# MEchaduino_03.net
KiCad netlist of a schematic drawn in EAGLE
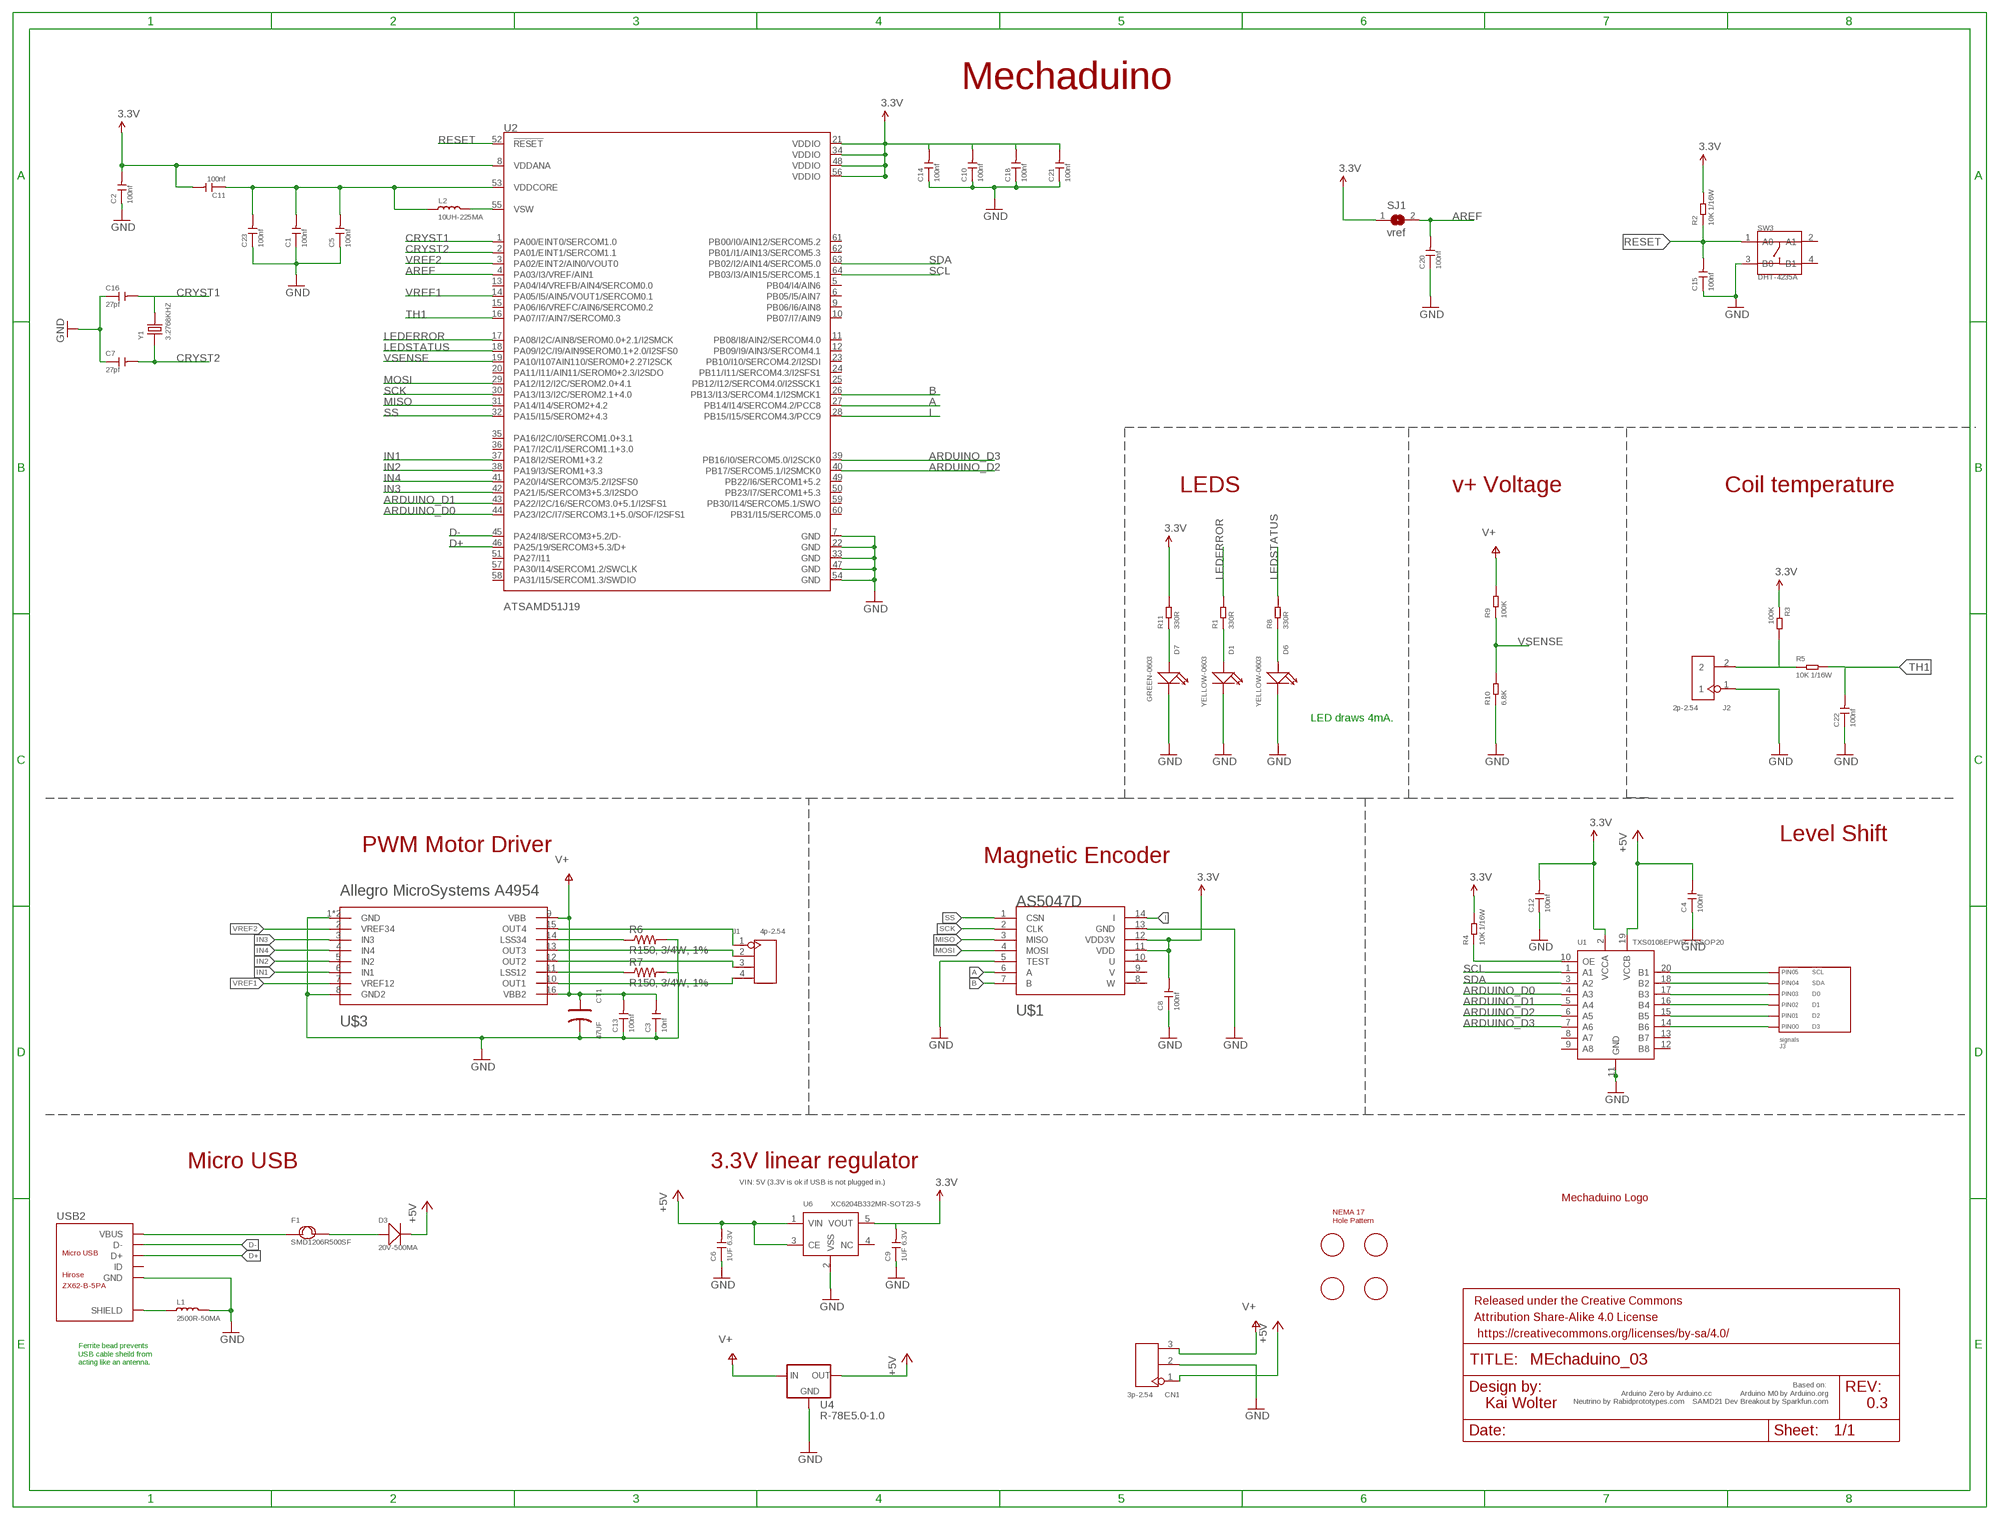
[diagram p0: schematic, sheet 1]

(export (version "E")
  (design (tool "Eeschema 10.0.6"))
  (components
    (comp (ref "C1")
      (value "100nf")
      (footprint "eagle-import:C0402")
      (fields (field (name "MPN") "CC0402KRX7R8BB104"))
      (libsource (lib "eagle-import") (part "CERAMIC-100NF-25V-10%-X7R(0402)"))
    )
    (comp (ref "C2")
      (value "100nf")
      (footprint "eagle-import:C0402")
      (fields (field (name "MPN") "CC0402KRX7R8BB104"))
      (libsource (lib "eagle-import") (part "CERAMIC-100NF-25V-10%-X7R(0402)"))
    )
    (comp (ref "C3")
      (value "10nf")
      (footprint "eagle-import:C0603")
      (fields (field (name "MPN") "CC0603KRX7R9BB103"))
      (libsource (lib "eagle-import") (part "CERAMIC-10NF-50V-10%-X7R(0603)"))
    )
    (comp (ref "C4")
      (value "100nf")
      (footprint "eagle-import:C0402")
      (fields (field (name "MPN") "CC0402KRX7R8BB104"))
      (libsource (lib "eagle-import") (part "CERAMIC-100NF-25V-10%-X7R(0402)"))
    )
    (comp (ref "C5")
      (value "100nf")
      (footprint "eagle-import:C0402")
      (fields (field (name "MPN") "CC0402KRX7R8BB104"))
      (libsource (lib "eagle-import") (part "CERAMIC-100NF-25V-10%-X7R(0402)"))
    )
    (comp (ref "C6")
      (value "1UF 6.3V")
      (footprint "eagle-import:C0402")
      (fields (field (name "MPN") "CC0402KRX5R5BB105"))
      (libsource (lib "eagle-import") (part "CERAMIC-1UF-6.3V-10%-X5R(0402)"))
    )
    (comp (ref "C7")
      (value "27pf")
      (footprint "eagle-import:C0402")
      (fields (field (name "MPN") "CC0402JRNPO9BN270"))
      (libsource (lib "eagle-import") (part "CERAMIC-27PF-50V-5%-NPO(0402)"))
    )
    (comp (ref "C8")
      (value "100nf")
      (footprint "eagle-import:C0402")
      (fields (field (name "MPN") "CC0402KRX7R8BB104"))
      (libsource (lib "eagle-import") (part "CERAMIC-100NF-25V-10%-X7R(0402)"))
    )
    (comp (ref "C9")
      (value "1UF 6.3V")
      (footprint "eagle-import:C0402")
      (fields (field (name "MPN") "CC0402KRX5R5BB105"))
      (libsource (lib "eagle-import") (part "CERAMIC-1UF-6.3V-10%-X5R(0402)"))
    )
    (comp (ref "C10")
      (value "100nf")
      (footprint "eagle-import:C0402")
      (fields (field (name "MPN") "CC0402KRX7R8BB104"))
      (libsource (lib "eagle-import") (part "CERAMIC-100NF-25V-10%-X7R(0402)"))
    )
    (comp (ref "C11")
      (value "100nf")
      (footprint "eagle-import:C0402")
      (fields (field (name "MPN") "CC0402KRX7R8BB104"))
      (libsource (lib "eagle-import") (part "CERAMIC-100NF-25V-10%-X7R(0402)"))
    )
    (comp (ref "C12")
      (value "100nf")
      (footprint "eagle-import:C0402")
      (fields (field (name "MPN") "CC0402KRX7R8BB104"))
      (libsource (lib "eagle-import") (part "CERAMIC-100NF-25V-10%-X7R(0402)"))
    )
    (comp (ref "C13")
      (value "100nf")
      (footprint "eagle-import:C0603")
      (fields (field (name "MPN") "CC0603KRX7R9BB104"))
      (libsource (lib "eagle-import") (part "CERAMIC-100NF-50V-10%-X7R(0603)"))
    )
    (comp (ref "C14")
      (value "100nf")
      (footprint "eagle-import:C0402")
      (fields (field (name "MPN") "CC0402KRX7R8BB104"))
      (libsource (lib "eagle-import") (part "CERAMIC-100NF-25V-10%-X7R(0402)"))
    )
    (comp (ref "C15")
      (value "100nf")
      (footprint "eagle-import:C0402")
      (fields (field (name "MPN") "CC0402KRX7R8BB104"))
      (libsource (lib "eagle-import") (part "CERAMIC-100NF-25V-10%-X7R(0402)"))
    )
    (comp (ref "C16")
      (value "27pf")
      (footprint "eagle-import:C0402")
      (fields (field (name "MPN") "CC0402JRNPO9BN270"))
      (libsource (lib "eagle-import") (part "CERAMIC-27PF-50V-5%-NPO(0402)"))
    )
    (comp (ref "C18")
      (value "100nf")
      (footprint "eagle-import:C0402")
      (fields (field (name "MPN") "CC0402KRX7R8BB104"))
      (libsource (lib "eagle-import") (part "CERAMIC-100NF-25V-10%-X7R(0402)"))
    )
    (comp (ref "C20")
      (value "100nf")
      (footprint "eagle-import:C0402")
      (fields (field (name "MPN") "CC0402KRX7R8BB104"))
      (libsource (lib "eagle-import") (part "CERAMIC-100NF-25V-10%-X7R(0402)"))
    )
    (comp (ref "C21")
      (value "100nf")
      (footprint "eagle-import:C0402")
      (fields (field (name "MPN") "CC0402KRX7R8BB104"))
      (libsource (lib "eagle-import") (part "CERAMIC-100NF-25V-10%-X7R(0402)"))
    )
    (comp (ref "C22")
      (value "100nf")
      (footprint "eagle-import:C0402")
      (fields (field (name "MPN") "CC0402KRX7R8BB104"))
      (libsource (lib "eagle-import") (part "CERAMIC-100NF-25V-10%-X7R(0402)"))
    )
    (comp (ref "C23")
      (value "100nf")
      (footprint "eagle-import:C0402")
      (fields (field (name "MPN") "CC0402KRX7R8BB104"))
      (libsource (lib "eagle-import") (part "CERAMIC-100NF-25V-10%-X7R(0402)"))
    )
    (comp (ref "CN1")
      (value "3p-2.54")
      (footprint "eagle-import:H3-2.54")
      (libsource (lib "eagle-import") (part "DIP-BLACK-MALE-HEADER-VERT(3P-2.54)"))
    )
    (comp (ref "CT1")
      (value "47UF")
      (footprint "eagle-import:ELECTRO-SMD-C-6MM")
      (fields (field (name "MPN") "CS1E470M-CRE54"))
      (libsource (lib "eagle-import") (part "ALUMINUM-SMD-47UF-25V(D6.3-H5.3MM)"))
    )
    (comp (ref "D1")
      (value "YELLOW-0603")
      (footprint "eagle-import:LED-0603")
      (fields (field (name "MPN") "19-217-Y5C-AM1N1VY-3T"))
      (libsource (lib "eagle-import") (part "SMD-LED-CLEAR-YELLOW(0603)"))
    )
    (comp (ref "D3")
      (value "20V-500MA")
      (footprint "eagle-import:SOD-123")
      (fields (field (name "MPN") "SS0520-7-F"))
      (libsource (lib "eagle-import") (part "SMD-DIODE-SCHOTTKY-20V-500MA(SOD-123)"))
    )
    (comp (ref "D6")
      (value "YELLOW-0603")
      (footprint "eagle-import:LED-0603")
      (fields (field (name "MPN") "19-217-Y5C-AM1N1VY-3T"))
      (libsource (lib "eagle-import") (part "SMD-LED-CLEAR-YELLOW(0603)"))
    )
    (comp (ref "D7")
      (value "GREEN-0603")
      (footprint "eagle-import:LED-0603")
      (fields (field (name "MPN") "19-217-G7C-AN1P2-3T"))
      (libsource (lib "eagle-import") (part "SMD-LED-CLEAR-GREEN(0603)"))
    )
    (comp (ref "F1")
      (value "SMD1206R500SF")
      (footprint "eagle-import:F1206")
      (libsource (lib "eagle-import") (part "SMD-PPTC-500MA(1206)"))
    )
    (comp (ref "FRAME1")
      (value "FRAME-LEDGER")
      (footprint "eagle-import:CREATIVE_COMMONS")
      (libsource (lib "eagle-import") (part "FRAME-LEDGER"))
    )
    (comp (ref "J1")
      (value "4p-2.54")
      (footprint "eagle-import:H4-2.54")
      (fields (field (name "MPN") "P125-1104A0BS116A1"))
      (libsource (lib "eagle-import") (part "DIP-BLACK-MALE-HEADER-VERT(4P-2.54)"))
    )
    (comp (ref "J2")
      (value "2p-2.54")
      (footprint "eagle-import:H2-2.54")
      (fields (field (name "MPN") "P125-1102A0BS116A1"))
      (libsource (lib "eagle-import") (part "DIP-BLACK-MALE-HEADER-VERT(2P-2.54)"))
    )
    (comp (ref "J3")
      (value "signals")
      (footprint "eagle-import:PTH_2.54MM_01X06")
      (fields
        (field (name "LABEL00") "D3")
        (field (name "LABEL01") "D2")
        (field (name "LABEL02") "D1")
        (field (name "LABEL03") "D0")
        (field (name "LABEL04") "SDA")
        (field (name "LABEL05") "SCL")
      )
      (libsource (lib "eagle-import") (part "HEADER_01X06_PTH_2.54MM"))
    )
    (comp (ref "L1")
      (value "2500R-50MA")
      (footprint "eagle-import:L0603")
      (libsource (lib "eagle-import") (part "SMD-FERRITE-BEAD-2500R-50MA(0603)"))
    )
    (comp (ref "L2")
      (value "10UH-225MA")
      (footprint "eagle-import:L0806")
      (fields (field (name "MPN") "LQH2MCN100K02L"))
      (libsource (lib "eagle-import") (part "SMD-INDUCTOR-10UH-225MA-10%(0806)"))
    )
    (comp (ref "R1")
      (value "330R")
      (footprint "eagle-import:R0402")
      (fields (field (name "MPN") "RC0402FR-07330RL"))
      (libsource (lib "eagle-import") (part "SMD-RES-330R-1%-1/16W(0402)"))
    )
    (comp (ref "R2")
      (value "10K 1/16W")
      (footprint "eagle-import:R0402")
      (fields (field (name "MPN") "RC0402FR-0710KL"))
      (libsource (lib "eagle-import") (part "SMD-RES-10K-1%-1/16W(0402)"))
    )
    (comp (ref "R3")
      (value "100K")
      (footprint "eagle-import:R0402")
      (fields (field (name "MPN") "RC0402FR-07100KL"))
      (libsource (lib "eagle-import") (part "SMD-RES-100K-1%-1/16W(0402)"))
    )
    (comp (ref "R4")
      (value "10K 1/16W")
      (footprint "eagle-import:R0402")
      (fields (field (name "MPN") "RC0402FR-0710KL"))
      (libsource (lib "eagle-import") (part "SMD-RES-10K-1%-1/16W(0402)"))
    )
    (comp (ref "R5")
      (value "10K 1/16W")
      (footprint "eagle-import:R0402")
      (fields (field (name "MPN") "RC0402FR-0710KL"))
      (libsource (lib "eagle-import") (part "SMD-RES-10K-1%-1/16W(0402)"))
    )
    (comp (ref "R6")
      (value "R150, 3/4W, 1%")
      (footprint "eagle-import:R1206")
      (fields (field (name "MPN") "KRL1632E-M-R150-F-T5 "))
      (libsource (lib "eagle-import") (part "R-US_R1206"))
    )
    (comp (ref "R7")
      (value "R150, 3/4W, 1%")
      (footprint "eagle-import:R1206")
      (fields (field (name "MPN") "KRL1632E-M-R150-F-T5 "))
      (libsource (lib "eagle-import") (part "R-US_R1206"))
    )
    (comp (ref "R8")
      (value "330R")
      (footprint "eagle-import:R0402")
      (fields (field (name "MPN") "RC0402FR-07330RL"))
      (libsource (lib "eagle-import") (part "SMD-RES-330R-1%-1/16W(0402)"))
    )
    (comp (ref "R9")
      (value "100K")
      (footprint "eagle-import:R0402")
      (fields (field (name "MPN") "RC0402FR-07100KL"))
      (libsource (lib "eagle-import") (part "SMD-RES-100K-1%-1/16W(0402)"))
    )
    (comp (ref "R10")
      (value "6.8K")
      (footprint "eagle-import:R0603")
      (fields (field (name "MPN") "RC0805JR-07220KL"))
      (libsource (lib "eagle-import") (part "SMD-RES-6.8K-1%-1/10W(0603)"))
    )
    (comp (ref "R11")
      (value "330R")
      (footprint "eagle-import:R0402")
      (fields (field (name "MPN") "RC0402FR-07330RL"))
      (libsource (lib "eagle-import") (part "SMD-RES-330R-1%-1/16W(0402)"))
    )
    (comp (ref "SJ1")
      (value "vref")
      (footprint "eagle-import:SJ")
      (libsource (lib "eagle-import") (part "SJ"))
    )
    (comp (ref "SW3")
      (value "DHT-4235A")
      (footprint "eagle-import:SW4-SMD-4.2X3.2X2.5MM")
      (libsource (lib "eagle-import") (part "SMD-BUTTON-TOP-DHT-4235A(4P-4.2X3.2MM)"))
    )
    (comp (ref "U$1")
      (value "AS5047D")
      (footprint "eagle-import:TSSOP14")
      (fields (field (name "MPN") "AS5047D-ATSM "))
      (libsource (lib "eagle-import") (part "AS5047D"))
    )
    (comp (ref "U$2")
      (value "NEMA17_HOLE_PATTERNNEW")
      (footprint "eagle-import:NEMA17_HOLE_PATTERN_2")
      (libsource (lib "eagle-import") (part "NEMA17_HOLE_PATTERNNEW"))
    )
    (comp (ref "U$3")
      (value "Allegro MicroSystems A4954")
      (footprint "eagle-import:TSSOP16_THERM")
      (fields (field (name "MPN") "A4953ELJTR-T "))
      (libsource (lib "eagle-import") (part "AVAGO_DRIVERTHERM"))
    )
    (comp (ref "U$4")
      (value "MECHADUINO_LOGO")
      (footprint "eagle-import:MECHADUINO_LOGO")
      (libsource (lib "eagle-import") (part "MECHADUINO_LOGO"))
    )
    (comp (ref "U1")
      (value "TXS0108EPWR-TSSOP20")
      (footprint "eagle-import:TSSOP20-0.65-6.5X4.4MM")
      (fields (field (name "MPN") "TXS0108EPWR"))
      (libsource (lib "eagle-import") (part "LOGIC-TXS0108EPWR(TSSOP20)"))
    )
    (comp (ref "U2")
      (value "ATSAMD51J19")
      (footprint "eagle-import:TQFP64")
      (fields (field (name "MPN") "ATSAMD51J19A-AU"))
      (libsource (lib "eagle-import") (part "ATSAMD51J19"))
    )
    (comp (ref "U4")
      (value "R-78E5.0-1.0")
      (footprint "eagle-import:DC-DC_CONVERTER_78XX")
      (libsource (lib "eagle-import") (part "R-78E5.0-1.0"))
    )
    (comp (ref "U6")
      (value "XC6204B332MR-SOT23-5")
      (footprint "eagle-import:SOT-23-5")
      (fields (field (name "MPN") "XC6204B332MR"))
      (libsource (lib "eagle-import") (part "PMIC-LDO-XC6204B332MR(SOT23-5)"))
    )
    (comp (ref "USB2")
      (value "ZX62-B-5PA")
      (footprint "eagle-import:MICRO-USB5+6P-SMD-0.65-AB")
      (libsource (lib "eagle-import") (part "MICRO-USB-SMD(ZX62-B-5PA)"))
    )
    (comp (ref "Y1")
      (value "3.2768KHZ")
      (footprint "eagle-import:X2-SMD-L2.0X1.2X0.55MM")
      (fields (field (name "MPN") "FC-12M"))
      (libsource (lib "eagle-import") (part "SMD-CRYSTAL-32.768KHZ-12.5PF-20PPM-90K(2P-L2.0X1.2MM)"))
    )
  )
  (nets
    (net (code "1") (name "+5V") (class "Default")
      (node (ref "C4") (pin "2") (pinfunction "2_2") (pintype "passive"))
      (node (ref "C6") (pin "2") (pinfunction "2_2") (pintype "passive"))
      (node (ref "CN1") (pin "1") (pinfunction "P$1_1") (pintype "bidirectional"))
      (node (ref "D3") (pin "-") (pinfunction "-_-") (pintype "passive"))
      (node (ref "U1") (pin "19") (pinfunction "VCCB_19") (pintype "bidirectional"))
      (node (ref "U4") (pin "VOUT") (pinfunction "OUT_VOUT") (pintype "passive"))
      (node (ref "U6") (pin "1") (pinfunction "VIN_1") (pintype "input"))
      (node (ref "U6") (pin "3") (pinfunction "CE_3") (pintype "bidirectional"))
    )
    (net (code "2") (name "/ARDUINO_D0") (class "Default")
      (node (ref "U1") (pin "4") (pinfunction "A3_4") (pintype "bidirectional"))
      (node (ref "U2") (pin "44") (pinfunction "PA23/I2C/I7/SERCOM3.1+5.0/SOF/I2SFS1_44") (pintype "bidirectional"))
    )
    (net (code "3") (name "/ARDUINO_D1") (class "Default")
      (node (ref "U1") (pin "5") (pinfunction "A4_5") (pintype "bidirectional"))
      (node (ref "U2") (pin "43") (pinfunction "PA22/I2C/16/SERCOM3.0+5.1/I2SFS1_43") (pintype "bidirectional"))
    )
    (net (code "4") (name "/ARDUINO_D2") (class "Default")
      (node (ref "U1") (pin "6") (pinfunction "A5_6") (pintype "bidirectional"))
      (node (ref "U2") (pin "40") (pinfunction "PB17/SERCOM5.1/I2SMCK0_40") (pintype "bidirectional"))
    )
    (net (code "5") (name "/ARDUINO_D3") (class "Default")
      (node (ref "U1") (pin "7") (pinfunction "A6_7") (pintype "bidirectional"))
      (node (ref "U2") (pin "39") (pinfunction "PB16/I0/SERCOM5.0/I2SCK0_39") (pintype "bidirectional"))
    )
    (net (code "6") (name "/AREF") (class "Default")
      (node (ref "C20") (pin "2") (pinfunction "2_2") (pintype "passive"))
      (node (ref "SJ1") (pin "2") (pinfunction "2_2") (pintype "passive"))
      (node (ref "U2") (pin "4") (pinfunction "PA03/I3/VREF/AIN1_4") (pintype "bidirectional"))
    )
    (net (code "7") (name "/CRYST1") (class "Default")
      (node (ref "C16") (pin "2") (pinfunction "2_2") (pintype "passive"))
      (node (ref "U2") (pin "1") (pinfunction "PA00/EINT0/SERCOM1.0_1") (pintype "bidirectional"))
      (node (ref "Y1") (pin "2") (pinfunction "2_2") (pintype "passive"))
    )
    (net (code "8") (name "/CRYST2") (class "Default")
      (node (ref "C7") (pin "2") (pinfunction "2_2") (pintype "passive"))
      (node (ref "U2") (pin "2") (pinfunction "PA01/EINT1/SERCOM1.1_2") (pintype "bidirectional"))
      (node (ref "Y1") (pin "1") (pinfunction "1_1") (pintype "passive"))
    )
    (net (code "9") (name "/LEDERROR") (class "Default")
      (node (ref "R1") (pin "2") (pinfunction "2_2") (pintype "passive"))
      (node (ref "U2") (pin "17") (pinfunction "PA08/I2C/AIN8/SEROM0.0+2.1/I2SMCK_17") (pintype "bidirectional"))
    )
    (net (code "10") (name "/LEDSTATUS") (class "Default")
      (node (ref "R8") (pin "2") (pinfunction "2_2") (pintype "passive"))
      (node (ref "U2") (pin "18") (pinfunction "PA09/I2C/I9/AIN9SEROM0.1+2.0/I2SFS0_18") (pintype "bidirectional"))
    )
    (net (code "11") (name "/SCL") (class "Default")
      (node (ref "U1") (pin "1") (pinfunction "A1_1") (pintype "bidirectional"))
      (node (ref "U2") (pin "64") (pinfunction "PB03/I3/AIN15/SERCOM5.1_64") (pintype "bidirectional"))
    )
    (net (code "12") (name "/SDA") (class "Default")
      (node (ref "U1") (pin "3") (pinfunction "A2_3") (pintype "bidirectional"))
      (node (ref "U2") (pin "63") (pinfunction "PB02/I2/AIN14/SERCOM5.0_63") (pintype "bidirectional"))
    )
    (net (code "13") (name "/VSENSE") (class "Default")
      (node (ref "R10") (pin "2") (pinfunction "2_2") (pintype "passive"))
      (node (ref "R9") (pin "1") (pinfunction "1_1") (pintype "passive"))
      (node (ref "U2") (pin "19") (pinfunction "PA10/I107AIN110/SEROM0+2.27I2SCK_19") (pintype "bidirectional"))
    )
    (net (code "14") (name "3.3V") (class "Default")
      (node (ref "C10") (pin "2") (pinfunction "2_2") (pintype "passive"))
      (node (ref "C11") (pin "2") (pinfunction "2_2") (pintype "passive"))
      (node (ref "C12") (pin "2") (pinfunction "2_2") (pintype "passive"))
      (node (ref "C14") (pin "2") (pinfunction "2_2") (pintype "passive"))
      (node (ref "C18") (pin "2") (pinfunction "2_2") (pintype "passive"))
      (node (ref "C2") (pin "2") (pinfunction "2_2") (pintype "passive"))
      (node (ref "C21") (pin "2") (pinfunction "2_2") (pintype "passive"))
      (node (ref "C8") (pin "2") (pinfunction "2_2") (pintype "passive"))
      (node (ref "C9") (pin "2") (pinfunction "2_2") (pintype "passive"))
      (node (ref "R11") (pin "2") (pinfunction "2_2") (pintype "passive"))
      (node (ref "R2") (pin "2") (pinfunction "2_2") (pintype "passive"))
      (node (ref "R3") (pin "1") (pinfunction "1_1") (pintype "passive"))
      (node (ref "R4") (pin "2") (pinfunction "2_2") (pintype "passive"))
      (node (ref "SJ1") (pin "1") (pinfunction "1_1") (pintype "passive"))
      (node (ref "U$1") (pin "11") (pinfunction "VDD_11") (pintype "bidirectional"))
      (node (ref "U$1") (pin "12") (pinfunction "VDD3V_12") (pintype "bidirectional"))
      (node (ref "U1") (pin "2") (pinfunction "VCCA_2") (pintype "bidirectional"))
      (node (ref "U2") (pin "21") (pinfunction "VDDIO_21") (pintype "bidirectional"))
      (node (ref "U2") (pin "34") (pinfunction "VDDIO_34") (pintype "bidirectional"))
      (node (ref "U2") (pin "48") (pinfunction "VDDIO_48") (pintype "bidirectional"))
      (node (ref "U2") (pin "56") (pinfunction "VDDIO_56") (pintype "bidirectional"))
      (node (ref "U2") (pin "8") (pinfunction "VDDANA_8") (pintype "bidirectional"))
      (node (ref "U6") (pin "5") (pinfunction "VOUT_5") (pintype "output"))
    )
    (net (code "15") (name "A") (class "Default")
      (node (ref "U$1") (pin "6") (pinfunction "A_6") (pintype "bidirectional"))
      (node (ref "U2") (pin "27") (pinfunction "PB14/I14/SERCOM4.2/PCC8_27") (pintype "bidirectional"))
    )
    (net (code "16") (name "B") (class "Default")
      (node (ref "U$1") (pin "7") (pinfunction "B_7") (pintype "bidirectional"))
      (node (ref "U2") (pin "26") (pinfunction "PB13/I13/SERCOM4.1/I2SMCK1_26") (pintype "bidirectional"))
    )
    (net (code "17") (name "D+") (class "Default")
      (node (ref "U2") (pin "46") (pinfunction "PA25/19/SERCOM3+5.3/D+_46") (pintype "bidirectional"))
      (node (ref "USB2") (pin "3") (pinfunction "D+_3") (pintype "bidirectional"))
    )
    (net (code "18") (name "D-") (class "Default")
      (node (ref "U2") (pin "45") (pinfunction "PA24/I8/SERCOM3+5.2/D-_45") (pintype "bidirectional"))
      (node (ref "USB2") (pin "2") (pinfunction "D-_2") (pintype "bidirectional"))
    )
    (net (code "19") (name "GND") (class "Default")
      (node (ref "C1") (pin "1") (pinfunction "1_1") (pintype "passive"))
      (node (ref "C10") (pin "1") (pinfunction "1_1") (pintype "passive"))
      (node (ref "C12") (pin "1") (pinfunction "1_1") (pintype "passive"))
      (node (ref "C13") (pin "1") (pinfunction "1_1") (pintype "passive"))
      (node (ref "C14") (pin "1") (pinfunction "1_1") (pintype "passive"))
      (node (ref "C15") (pin "1") (pinfunction "1_1") (pintype "passive"))
      (node (ref "C16") (pin "1") (pinfunction "1_1") (pintype "passive"))
      (node (ref "C18") (pin "1") (pinfunction "1_1") (pintype "passive"))
      (node (ref "C2") (pin "1") (pinfunction "1_1") (pintype "passive"))
      (node (ref "C20") (pin "1") (pinfunction "1_1") (pintype "passive"))
      (node (ref "C21") (pin "1") (pinfunction "1_1") (pintype "passive"))
      (node (ref "C22") (pin "1") (pinfunction "1_1") (pintype "passive"))
      (node (ref "C23") (pin "1") (pinfunction "1_1") (pintype "passive"))
      (node (ref "C3") (pin "1") (pinfunction "1_1") (pintype "passive"))
      (node (ref "C4") (pin "1") (pinfunction "1_1") (pintype "passive"))
      (node (ref "C5") (pin "1") (pinfunction "1_1") (pintype "passive"))
      (node (ref "C6") (pin "1") (pinfunction "1_1") (pintype "passive"))
      (node (ref "C7") (pin "1") (pinfunction "1_1") (pintype "passive"))
      (node (ref "C8") (pin "1") (pinfunction "1_1") (pintype "passive"))
      (node (ref "C9") (pin "1") (pinfunction "1_1") (pintype "passive"))
      (node (ref "CN1") (pin "2") (pinfunction "P$2_2") (pintype "bidirectional"))
      (node (ref "CT1") (pin "-") (pinfunction "-_-") (pintype "passive"))
      (node (ref "D1") (pin "-") (pinfunction "-_-") (pintype "passive"))
      (node (ref "D6") (pin "-") (pinfunction "-_-") (pintype "passive"))
      (node (ref "D7") (pin "-") (pinfunction "-_-") (pintype "passive"))
      (node (ref "J2") (pin "1") (pinfunction "1_1") (pintype "bidirectional"))
      (node (ref "L1") (pin "2") (pinfunction "2_2") (pintype "passive"))
      (node (ref "R10") (pin "1") (pinfunction "1_1") (pintype "passive"))
      (node (ref "R6") (pin "2") (pinfunction "2_2") (pintype "passive"))
      (node (ref "R7") (pin "2") (pinfunction "2_2") (pintype "passive"))
      (node (ref "SW3") (pin "3") (pinfunction "B0_3") (pintype "bidirectional"))
      (node (ref "U$1") (pin "13") (pinfunction "GND_13") (pintype "bidirectional"))
      (node (ref "U$1") (pin "5") (pinfunction "TEST_5") (pintype "bidirectional"))
      (node (ref "U$3") (pin "1") (pinfunction "GND_1") (pintype "bidirectional"))
      (node (ref "U$3") (pin "8") (pinfunction "GND2_8") (pintype "bidirectional"))
      (node (ref "U$3") (pin "P$1") (pinfunction "GND_P$1") (pintype "bidirectional"))
      (node (ref "U1") (pin "11") (pinfunction "GND_11") (pintype "bidirectional"))
      (node (ref "U2") (pin "22") (pinfunction "GND_22") (pintype "bidirectional"))
      (node (ref "U2") (pin "33") (pinfunction "GND_33") (pintype "bidirectional"))
      (node (ref "U2") (pin "47") (pinfunction "GND_47") (pintype "bidirectional"))
      (node (ref "U2") (pin "54") (pinfunction "GND_54") (pintype "bidirectional"))
      (node (ref "U2") (pin "7") (pinfunction "GND_7") (pintype "bidirectional"))
      (node (ref "U4") (pin "GND") (pinfunction "GND_GND") (pintype "input"))
      (node (ref "U6") (pin "2") (pinfunction "VSS_2") (pintype "power_in"))
      (node (ref "USB2") (pin "5") (pinfunction "GND_5") (pintype "power_in"))
    )
    (net (code "20") (name "I") (class "Default")
      (node (ref "U$1") (pin "14") (pinfunction "I_14") (pintype "bidirectional"))
      (node (ref "U2") (pin "28") (pinfunction "PB15/I15/SERCOM4.3/PCC9_28") (pintype "bidirectional"))
    )
    (net (code "21") (name "IN1") (class "Default")
      (node (ref "U$3") (pin "6") (pinfunction "IN1_6") (pintype "bidirectional"))
      (node (ref "U2") (pin "37") (pinfunction "PA18/I2/SEROM1+3.2_37") (pintype "bidirectional"))
    )
    (net (code "22") (name "IN2") (class "Default")
      (node (ref "U$3") (pin "5") (pinfunction "IN2_5") (pintype "bidirectional"))
      (node (ref "U2") (pin "38") (pinfunction "PA19/I3/SEROM1+3.3_38") (pintype "bidirectional"))
    )
    (net (code "23") (name "IN3") (class "Default")
      (node (ref "U$3") (pin "3") (pinfunction "IN3_3") (pintype "bidirectional"))
      (node (ref "U2") (pin "42") (pinfunction "PA21/I5/SERCOM3+5.3/I2SDO_42") (pintype "bidirectional"))
    )
    (net (code "24") (name "IN4") (class "Default")
      (node (ref "U$3") (pin "4") (pinfunction "IN4_4") (pintype "bidirectional"))
      (node (ref "U2") (pin "41") (pinfunction "PA20/I4/SERCOM3/5.2/I2SFS0_41") (pintype "bidirectional"))
    )
    (net (code "25") (name "MISO") (class "Default")
      (node (ref "U$1") (pin "3") (pinfunction "MISO_3") (pintype "bidirectional"))
      (node (ref "U2") (pin "31") (pinfunction "PA14/I14/SEROM2+4.2_31") (pintype "bidirectional"))
    )
    (net (code "26") (name "MOSI") (class "Default")
      (node (ref "U$1") (pin "4") (pinfunction "MOSI_4") (pintype "bidirectional"))
      (node (ref "U2") (pin "29") (pinfunction "PA12/I12/I2C/SEROM2.0+4.1_29") (pintype "bidirectional"))
    )
    (net (code "27") (name "Net-(D1-Pad+)") (class "Default")
      (node (ref "D1") (pin "+") (pinfunction "+_+") (pintype "passive"))
      (node (ref "R1") (pin "1") (pinfunction "1_1") (pintype "passive"))
    )
    (net (code "28") (name "Net-(D3-Pad+)") (class "Default")
      (node (ref "D3") (pin "+") (pinfunction "+_+") (pintype "passive"))
      (node (ref "F1") (pin "2") (pinfunction "2_2") (pintype "bidirectional"))
    )
    (net (code "29") (name "Net-(D6-Pad+)") (class "Default")
      (node (ref "D6") (pin "+") (pinfunction "+_+") (pintype "passive"))
      (node (ref "R8") (pin "1") (pinfunction "1_1") (pintype "passive"))
    )
    (net (code "30") (name "Net-(D7-Pad+)") (class "Default")
      (node (ref "D7") (pin "+") (pinfunction "+_+") (pintype "passive"))
      (node (ref "R11") (pin "1") (pinfunction "1_1") (pintype "passive"))
    )
    (net (code "31") (name "Net-(J1-P$1)") (class "Default")
      (node (ref "J1") (pin "1") (pinfunction "P$1_1") (pintype "bidirectional"))
      (node (ref "U$3") (pin "15") (pinfunction "OUT4_15") (pintype "bidirectional"))
    )
    (net (code "32") (name "Net-(J1-P$2)") (class "Default")
      (node (ref "J1") (pin "2") (pinfunction "P$2_2") (pintype "bidirectional"))
      (node (ref "U$3") (pin "13") (pinfunction "OUT3_13") (pintype "bidirectional"))
    )
    (net (code "33") (name "Net-(J1-P$3)") (class "Default")
      (node (ref "J1") (pin "3") (pinfunction "P$3_3") (pintype "bidirectional"))
      (node (ref "U$3") (pin "12") (pinfunction "OUT2_12") (pintype "bidirectional"))
    )
    (net (code "34") (name "Net-(J1-P$4)") (class "Default")
      (node (ref "J1") (pin "4") (pinfunction "P$4_4") (pintype "bidirectional"))
      (node (ref "U$3") (pin "10") (pinfunction "OUT1_10") (pintype "bidirectional"))
    )
    (net (code "35") (name "Net-(J2-Pad2)") (class "Default")
      (node (ref "J2") (pin "2") (pinfunction "2_2") (pintype "bidirectional"))
      (node (ref "R3") (pin "2") (pinfunction "2_2") (pintype "passive"))
      (node (ref "R5") (pin "1") (pinfunction "1_1") (pintype "passive"))
    )
    (net (code "36") (name "Net-(J3-PIN0)") (class "Default")
      (node (ref "J3") (pin "P$1") (pinfunction "PIN0_P$1") (pintype "bidirectional"))
      (node (ref "U1") (pin "14") (pinfunction "B6_14") (pintype "bidirectional"))
    )
    (net (code "37") (name "Net-(J3-PIN1)") (class "Default")
      (node (ref "J3") (pin "P$2") (pinfunction "PIN1_P$2") (pintype "bidirectional"))
      (node (ref "U1") (pin "15") (pinfunction "B5_15") (pintype "bidirectional"))
    )
    (net (code "38") (name "Net-(J3-PIN2)") (class "Default")
      (node (ref "J3") (pin "P$3") (pinfunction "PIN2_P$3") (pintype "bidirectional"))
      (node (ref "U1") (pin "16") (pinfunction "B4_16") (pintype "bidirectional"))
    )
    (net (code "39") (name "Net-(J3-PIN3)") (class "Default")
      (node (ref "J3") (pin "P$4") (pinfunction "PIN3_P$4") (pintype "bidirectional"))
      (node (ref "U1") (pin "17") (pinfunction "B3_17") (pintype "bidirectional"))
    )
    (net (code "40") (name "Net-(J3-PIN4)") (class "Default")
      (node (ref "J3") (pin "P$5") (pinfunction "PIN4_P$5") (pintype "bidirectional"))
      (node (ref "U1") (pin "18") (pinfunction "B2_18") (pintype "bidirectional"))
    )
    (net (code "41") (name "Net-(J3-PIN5)") (class "Default")
      (node (ref "J3") (pin "P$6") (pinfunction "PIN5_P$6") (pintype "bidirectional"))
      (node (ref "U1") (pin "20") (pinfunction "B1_20") (pintype "bidirectional"))
    )
    (net (code "42") (name "Net-(L1-Pad1)") (class "Default")
      (node (ref "L1") (pin "1") (pinfunction "1_1") (pintype "passive"))
      (node (ref "USB2") (pin "P1") (pinfunction "SHIELD_P1") (pintype "power_in"))
      (node (ref "USB2") (pin "P2") (pinfunction "SHIELD_P2") (pintype "power_in"))
      (node (ref "USB2") (pin "P3") (pinfunction "SHIELD_P3") (pintype "power_in"))
      (node (ref "USB2") (pin "P4") (pinfunction "SHIELD_P4") (pintype "power_in"))
      (node (ref "USB2") (pin "P5") (pinfunction "SHIELD_P5") (pintype "power_in"))
      (node (ref "USB2") (pin "P6") (pinfunction "SHIELD_P6") (pintype "power_in"))
    )
    (net (code "43") (name "Net-(U$3-LSS12)") (class "Default")
      (node (ref "R7") (pin "1") (pinfunction "1_1") (pintype "passive"))
      (node (ref "U$3") (pin "11") (pinfunction "LSS12_11") (pintype "bidirectional"))
    )
    (net (code "44") (name "Net-(U$3-LSS34)") (class "Default")
      (node (ref "R6") (pin "1") (pinfunction "1_1") (pintype "passive"))
      (node (ref "U$3") (pin "14") (pinfunction "LSS34_14") (pintype "bidirectional"))
    )
    (net (code "45") (name "Net-(U1-OE)") (class "Default")
      (node (ref "R4") (pin "1") (pinfunction "1_1") (pintype "passive"))
      (node (ref "U1") (pin "10") (pinfunction "OE_10") (pintype "bidirectional"))
    )
    (net (code "46") (name "Net-(U2-VDDCORE)") (class "Default")
      (node (ref "C1") (pin "2") (pinfunction "2_2") (pintype "passive"))
      (node (ref "C11") (pin "1") (pinfunction "1_1") (pintype "passive"))
      (node (ref "C23") (pin "2") (pinfunction "2_2") (pintype "passive"))
      (node (ref "C5") (pin "2") (pinfunction "2_2") (pintype "passive"))
      (node (ref "L2") (pin "1") (pinfunction "1_1") (pintype "passive"))
      (node (ref "U2") (pin "53") (pinfunction "VDDCORE_53") (pintype "bidirectional"))
    )
    (net (code "47") (name "Net-(U2-VSW)") (class "Default")
      (node (ref "L2") (pin "2") (pinfunction "2_2") (pintype "passive"))
      (node (ref "U2") (pin "55") (pinfunction "VSW_55") (pintype "bidirectional"))
    )
    (net (code "48") (name "Net-(USB2-VBUS)") (class "Default")
      (node (ref "F1") (pin "1") (pinfunction "1_1") (pintype "bidirectional"))
      (node (ref "USB2") (pin "1") (pinfunction "VBUS_1") (pintype "power_in"))
    )
    (net (code "49") (name "RESET") (class "Default")
      (node (ref "C15") (pin "2") (pinfunction "2_2") (pintype "passive"))
      (node (ref "R2") (pin "1") (pinfunction "1_1") (pintype "passive"))
      (node (ref "SW3") (pin "1") (pinfunction "A0_1") (pintype "bidirectional"))
      (node (ref "U2") (pin "52") (pinfunction "~{RESET}_52") (pintype "bidirectional"))
    )
    (net (code "50") (name "SCK") (class "Default")
      (node (ref "U$1") (pin "2") (pinfunction "CLK_2") (pintype "bidirectional"))
      (node (ref "U2") (pin "30") (pinfunction "PA13/I13/I2C/SEROM2.1+4.0_30") (pintype "bidirectional"))
    )
    (net (code "51") (name "SS") (class "Default")
      (node (ref "U$1") (pin "1") (pinfunction "CSN_1") (pintype "bidirectional"))
      (node (ref "U2") (pin "32") (pinfunction "PA15/I15/SEROM2+4.3_32") (pintype "bidirectional"))
    )
    (net (code "52") (name "TH1") (class "Default")
      (node (ref "C22") (pin "2") (pinfunction "2_2") (pintype "passive"))
      (node (ref "R5") (pin "2") (pinfunction "2_2") (pintype "passive"))
      (node (ref "U2") (pin "16") (pinfunction "PA07/I7/AIN7/SERCOM0.3_16") (pintype "bidirectional"))
    )
    (net (code "53") (name "V+") (class "Default")
      (node (ref "C13") (pin "2") (pinfunction "2_2") (pintype "passive"))
      (node (ref "C3") (pin "2") (pinfunction "2_2") (pintype "passive"))
      (node (ref "CN1") (pin "3") (pinfunction "P$3_3") (pintype "bidirectional"))
      (node (ref "CT1") (pin "+") (pinfunction "+_+") (pintype "passive"))
      (node (ref "R9") (pin "2") (pinfunction "2_2") (pintype "passive"))
      (node (ref "U$3") (pin "16") (pinfunction "VBB2_16") (pintype "bidirectional"))
      (node (ref "U$3") (pin "9") (pinfunction "VBB_9") (pintype "bidirectional"))
      (node (ref "U4") (pin "VIN") (pinfunction "IN_VIN") (pintype "input"))
    )
    (net (code "54") (name "VREF1") (class "Default")
      (node (ref "U$3") (pin "7") (pinfunction "VREF12_7") (pintype "bidirectional"))
      (node (ref "U2") (pin "14") (pinfunction "PA05/I5/AIN5/VOUT1/SERCOM0.1_14") (pintype "bidirectional"))
    )
    (net (code "55") (name "VREF2") (class "Default")
      (node (ref "U$3") (pin "2") (pinfunction "VREF34_2") (pintype "bidirectional"))
      (node (ref "U2") (pin "3") (pinfunction "PA02/EINT2/AIN0/VOUT0_3") (pintype "bidirectional"))
    )
    (net (code "56") (name "unconnected-(SW3-A1-Pad2)") (class "Default")
      (node (ref "SW3") (pin "2") (pinfunction "A1_2") (pintype "bidirectional"))
    )
    (net (code "57") (name "unconnected-(SW3-B1-Pad4)") (class "Default")
      (node (ref "SW3") (pin "4") (pinfunction "B1_4") (pintype "bidirectional"))
    )
    (net (code "58") (name "unconnected-(U$1-U-Pad10)") (class "Default")
      (node (ref "U$1") (pin "10") (pinfunction "U_10") (pintype "bidirectional"))
    )
    (net (code "59") (name "unconnected-(U$1-V-Pad9)") (class "Default")
      (node (ref "U$1") (pin "9") (pinfunction "V_9") (pintype "bidirectional"))
    )
    (net (code "60") (name "unconnected-(U$1-W-Pad8)") (class "Default")
      (node (ref "U$1") (pin "8") (pinfunction "W_8") (pintype "bidirectional"))
    )
    (net (code "61") (name "unconnected-(U1-A7-Pad8)") (class "Default")
      (node (ref "U1") (pin "8") (pinfunction "A7_8") (pintype "bidirectional"))
    )
    (net (code "62") (name "unconnected-(U1-A8-Pad9)") (class "Default")
      (node (ref "U1") (pin "9") (pinfunction "A8_9") (pintype "bidirectional"))
    )
    (net (code "63") (name "unconnected-(U1-B7-Pad13)") (class "Default")
      (node (ref "U1") (pin "13") (pinfunction "B7_13") (pintype "bidirectional"))
    )
    (net (code "64") (name "unconnected-(U1-B8-Pad12)") (class "Default")
      (node (ref "U1") (pin "12") (pinfunction "B8_12") (pintype "bidirectional"))
    )
    (net (code "65") (name "unconnected-(U2-PA04{slash}I4{slash}VREFB{slash}AIN4{slash}SERCOM0.0-Pad13)") (class "Default")
      (node (ref "U2") (pin "13") (pinfunction "PA04/I4/VREFB/AIN4/SERCOM0.0_13") (pintype "bidirectional"))
    )
    (net (code "66") (name "unconnected-(U2-PA06{slash}I6{slash}VREFC{slash}AIN6{slash}SERCOM0.2-Pad15)") (class "Default")
      (node (ref "U2") (pin "15") (pinfunction "PA06/I6/VREFC/AIN6/SERCOM0.2_15") (pintype "bidirectional"))
    )
    (net (code "67") (name "unconnected-(U2-PA11{slash}I11{slash}AIN11{slash}SEROM0+2.3{slash}I2SDO-Pad20)") (class "Default")
      (node (ref "U2") (pin "20") (pinfunction "PA11/I11/AIN11/SEROM0+2.3/I2SDO_20") (pintype "bidirectional"))
    )
    (net (code "68") (name "unconnected-(U2-PA16{slash}I2C{slash}I0{slash}SERCOM1.0+3.1-Pad35)") (class "Default")
      (node (ref "U2") (pin "35") (pinfunction "PA16/I2C/I0/SERCOM1.0+3.1_35") (pintype "bidirectional"))
    )
    (net (code "69") (name "unconnected-(U2-PA17{slash}I2C{slash}I1{slash}SERCOM1.1+3.0-Pad36)") (class "Default")
      (node (ref "U2") (pin "36") (pinfunction "PA17/I2C/I1/SERCOM1.1+3.0_36") (pintype "bidirectional"))
    )
    (net (code "70") (name "unconnected-(U2-PA27{slash}I11-Pad51)") (class "Default")
      (node (ref "U2") (pin "51") (pinfunction "PA27/I11_51") (pintype "bidirectional"))
    )
    (net (code "71") (name "unconnected-(U2-PA30{slash}I14{slash}SERCOM1.2{slash}SWCLK-Pad57)") (class "Default")
      (node (ref "U2") (pin "57") (pinfunction "PA30/I14/SERCOM1.2/SWCLK_57") (pintype "bidirectional"))
    )
    (net (code "72") (name "unconnected-(U2-PA31{slash}I15{slash}SERCOM1.3{slash}SWDIO-Pad58)") (class "Default")
      (node (ref "U2") (pin "58") (pinfunction "PA31/I15/SERCOM1.3/SWDIO_58") (pintype "bidirectional"))
    )
    (net (code "73") (name "unconnected-(U2-PB00{slash}I0{slash}AIN12{slash}SERCOM5.2-Pad61)") (class "Default")
      (node (ref "U2") (pin "61") (pinfunction "PB00/I0/AIN12/SERCOM5.2_61") (pintype "bidirectional"))
    )
    (net (code "74") (name "unconnected-(U2-PB01{slash}I1{slash}AIN13{slash}SERCOM5.3-Pad62)") (class "Default")
      (node (ref "U2") (pin "62") (pinfunction "PB01/I1/AIN13/SERCOM5.3_62") (pintype "bidirectional"))
    )
    (net (code "75") (name "unconnected-(U2-PB04{slash}I4{slash}AIN6-Pad5)") (class "Default")
      (node (ref "U2") (pin "5") (pinfunction "PB04/I4/AIN6_5") (pintype "bidirectional"))
    )
    (net (code "76") (name "unconnected-(U2-PB05{slash}I5{slash}AIN7-Pad6)") (class "Default")
      (node (ref "U2") (pin "6") (pinfunction "PB05/I5/AIN7_6") (pintype "bidirectional"))
    )
    (net (code "77") (name "unconnected-(U2-PB06{slash}I6{slash}AIN8-Pad9)") (class "Default")
      (node (ref "U2") (pin "9") (pinfunction "PB06/I6/AIN8_9") (pintype "bidirectional"))
    )
    (net (code "78") (name "unconnected-(U2-PB07{slash}I7{slash}AIN9-Pad10)") (class "Default")
      (node (ref "U2") (pin "10") (pinfunction "PB07/I7/AIN9_10") (pintype "bidirectional"))
    )
    (net (code "79") (name "unconnected-(U2-PB08{slash}I8{slash}AIN2{slash}SERCOM4.0-Pad11)") (class "Default")
      (node (ref "U2") (pin "11") (pinfunction "PB08/I8/AIN2/SERCOM4.0_11") (pintype "bidirectional"))
    )
    (net (code "80") (name "unconnected-(U2-PB09{slash}I9{slash}AIN3{slash}SERCOM4.1-Pad12)") (class "Default")
      (node (ref "U2") (pin "12") (pinfunction "PB09/I9/AIN3/SERCOM4.1_12") (pintype "bidirectional"))
    )
    (net (code "81") (name "unconnected-(U2-PB10{slash}I10{slash}SERCOM4.2{slash}I2SDI-Pad23)") (class "Default")
      (node (ref "U2") (pin "23") (pinfunction "PB10/I10/SERCOM4.2/I2SDI_23") (pintype "bidirectional"))
    )
    (net (code "82") (name "unconnected-(U2-PB11{slash}I11{slash}SERCOM4.3{slash}I2SFS1-Pad24)") (class "Default")
      (node (ref "U2") (pin "24") (pinfunction "PB11/I11/SERCOM4.3/I2SFS1_24") (pintype "bidirectional"))
    )
    (net (code "83") (name "unconnected-(U2-PB12{slash}I12{slash}SERCOM4.0{slash}I2SSCK1-Pad25)") (class "Default")
      (node (ref "U2") (pin "25") (pinfunction "PB12/I12/SERCOM4.0/I2SSCK1_25") (pintype "bidirectional"))
    )
    (net (code "84") (name "unconnected-(U2-PB22{slash}I6{slash}SERCOM1+5.2-Pad49)") (class "Default")
      (node (ref "U2") (pin "49") (pinfunction "PB22/I6/SERCOM1+5.2_49") (pintype "bidirectional"))
    )
    (net (code "85") (name "unconnected-(U2-PB23{slash}I7{slash}SERCOM1+5.3-Pad50)") (class "Default")
      (node (ref "U2") (pin "50") (pinfunction "PB23/I7/SERCOM1+5.3_50") (pintype "bidirectional"))
    )
    (net (code "86") (name "unconnected-(U2-PB30{slash}I14{slash}SERCOM5.1{slash}SWO-Pad59)") (class "Default")
      (node (ref "U2") (pin "59") (pinfunction "PB30/I14/SERCOM5.1/SWO_59") (pintype "bidirectional"))
    )
    (net (code "87") (name "unconnected-(U2-PB31{slash}I15{slash}SERCOM5.0-Pad60)") (class "Default")
      (node (ref "U2") (pin "60") (pinfunction "PB31/I15/SERCOM5.0_60") (pintype "bidirectional"))
    )
    (net (code "88") (name "unconnected-(U6-NC-Pad4)") (class "Default")
      (node (ref "U6") (pin "4") (pinfunction "NC_4") (pintype "no_connect"))
    )
    (net (code "89") (name "unconnected-(USB2-ID-Pad4)") (class "Default")
      (node (ref "USB2") (pin "4") (pinfunction "ID_4") (pintype "bidirectional"))
    )
  )
)
